# 04-RS485_CAN.net
KiCad netlist of a schematic drawn in Altium Designer
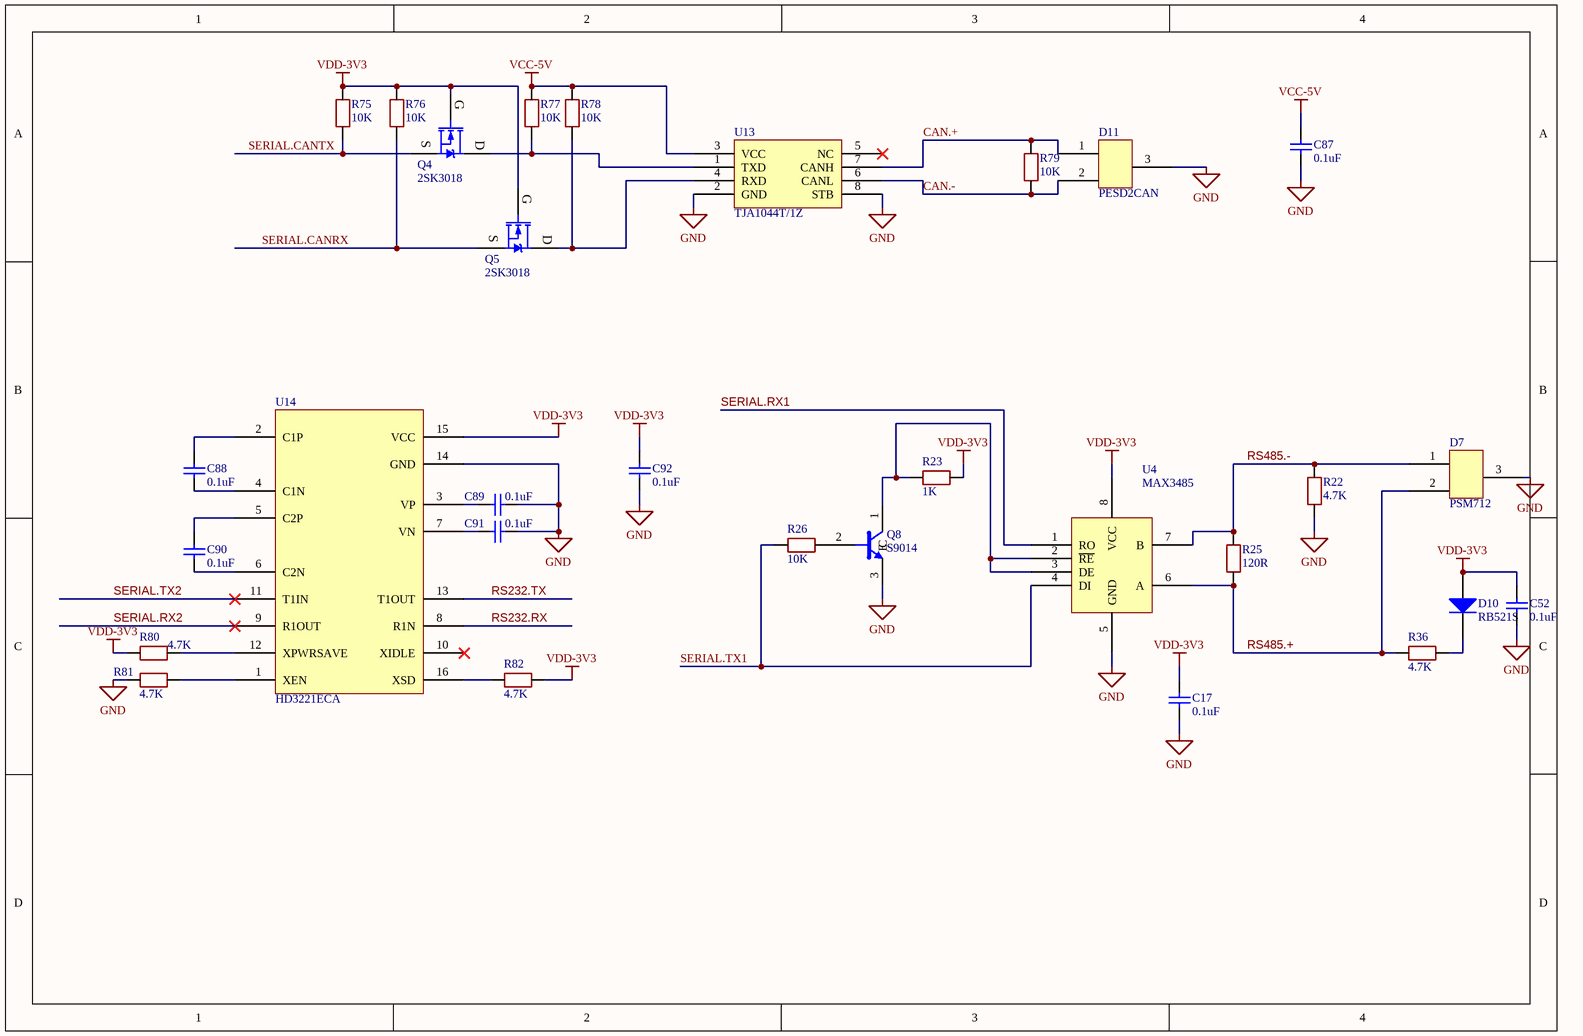
[diagram p0: 04-RS485+CAN.SchDoc]

(export (version "E")
  (design (tool "Eeschema 10.0.6"))
  (components
    (comp (ref "C17") (value "0.1uF") (footprint "C0402") (libsource (lib "PCB_Project") (part "CAP1")))
    (comp (ref "C52") (value "0.1uF") (footprint "C0402") (libsource (lib "PCB_Project") (part "CAP1")))
    (comp (ref "C87") (value "0.1uF") (footprint "C0402") (libsource (lib "PCB_Project") (part "CAP1")))
    (comp (ref "C88") (value "0.1uF") (footprint "C0402") (libsource (lib "PCB_Project") (part "CAP1")))
    (comp (ref "C89") (value "0.1uF") (footprint "C0402") (libsource (lib "PCB_Project") (part "CAP1")))
    (comp (ref "C90") (value "0.1uF") (footprint "C0402") (libsource (lib "PCB_Project") (part "CAP1")))
    (comp (ref "C91") (value "0.1uF") (footprint "C0402") (libsource (lib "PCB_Project") (part "CAP1")))
    (comp (ref "C92") (value "0.1uF") (footprint "C0402") (libsource (lib "PCB_Project") (part "CAP1")))
    (comp (ref "D7")
      (value "PSM712")
      (footprint "SOT-23-3_L3.0-W1.7-P0.95-LS2.9-BR")
      (libsource (lib "Schlib1") (part "PESD2CAN"))
    )
    (comp (ref "D10")
      (value "RB521S")
      (footprint "SOD-523_L1.2-W0.8-LS1.6-RD")
      (libsource (lib "PCB_Project") (part "DIODE"))
    )
    (comp (ref "D11")
      (value "PESD2CAN")
      (footprint "SOT-23-3_L3.0-W1.7-P0.95-LS2.9-BR")
      (libsource (lib "Schlib1") (part "PESD2CAN"))
    )
    (comp (ref "Q4")
      (value "2SK3018")
      (footprint "SOT-23-3_L2.9-W1.6-P1.90-LS2.8-BR")
      (libsource (lib "PCB_Project") (part "2N7002"))
    )
    (comp (ref "Q5")
      (value "2SK3018")
      (footprint "SOT-23-3_L2.9-W1.6-P1.90-LS2.8-BR")
      (libsource (lib "PCB_Project") (part "2N7002"))
    )
    (comp (ref "Q8")
      (value "S9014")
      (footprint "SOT-23-3_L2.9-W1.6-P1.90-LS2.8-BR")
      (libsource (lib "PCB_Project") (part "NPN"))
    )
    (comp (ref "R22") (value "4.7K") (footprint "R0402") (libsource (lib "PCB_Project") (part "R")))
    (comp (ref "R23") (value "1K") (footprint "R0402") (libsource (lib "PCB_Project") (part "R")))
    (comp (ref "R25") (value "120R") (footprint "R0402") (libsource (lib "PCB_Project") (part "R")))
    (comp (ref "R26") (value "10K") (footprint "R0402") (libsource (lib "PCB_Project") (part "R")))
    (comp (ref "R36") (value "4.7K") (footprint "R0402") (libsource (lib "PCB_Project") (part "R")))
    (comp (ref "R75") (value "10K") (footprint "R0402") (libsource (lib "PCB_Project") (part "R")))
    (comp (ref "R76") (value "10K") (footprint "R0402") (libsource (lib "PCB_Project") (part "R")))
    (comp (ref "R77") (value "10K") (footprint "R0402") (libsource (lib "PCB_Project") (part "R")))
    (comp (ref "R78") (value "10K") (footprint "R0402") (libsource (lib "PCB_Project") (part "R")))
    (comp (ref "R79") (value "10K") (footprint "R0402") (libsource (lib "PCB_Project") (part "R")))
    (comp (ref "R80") (value "4.7K") (footprint "R0402") (libsource (lib "PCB_Project") (part "R")))
    (comp (ref "R81") (value "4.7K") (footprint "R0402") (libsource (lib "PCB_Project") (part "R")))
    (comp (ref "R82") (value "4.7K") (footprint "R0402") (libsource (lib "PCB_Project") (part "R")))
    (comp (ref "U4")
      (value "MAX3485")
      (footprint "SOIC-8_L4.9-W3.9-P1.27-LS6.0-BL")
      (libsource (lib "Schlib1") (part "MAX3485"))
    )
    (comp (ref "U13")
      (value "TJA1044T/1Z")
      (footprint "SOIC-8_L4.9-W3.9-P1.27-LS6.0-BL")
      (libsource (lib "Schlib1") (part "TJA1044T/1Z"))
    )
    (comp (ref "U14")
      (value "HD3221ECA")
      (footprint "SSOP-16_L6.2-W5.3-P0.65-LS7.8-BL")
      (libsource (lib "Sheet2") (part "HD3221ECA"))
    )
  )
  (nets
    (net (code "1") (name "/CAN.+") (class "Default")
      (node (ref "D11") (pin "1") (pintype "passive"))
      (node (ref "R79") (pin "2") (pinfunction "2_2") (pintype "passive"))
      (node (ref "U13") (pin "7") (pinfunction "CANH_7") (pintype "passive"))
    )
    (net (code "2") (name "/CAN.-") (class "Default")
      (node (ref "D11") (pin "2") (pintype "passive"))
      (node (ref "R79") (pin "1") (pinfunction "1_1") (pintype "passive"))
      (node (ref "U13") (pin "6") (pinfunction "CANL_6") (pintype "passive"))
    )
    (net (code "3") (name "/RS232.RX") (class "Default")
      (node (ref "U14") (pin "8") (pinfunction "R1N_8") (pintype "passive"))
    )
    (net (code "4") (name "/RS232.TX") (class "Default")
      (node (ref "U14") (pin "13") (pinfunction "T1OUT_13") (pintype "passive"))
    )
    (net (code "5") (name "/RS485.+") (class "Default")
      (node (ref "D7") (pin "2") (pintype "passive"))
      (node (ref "R25") (pin "2") (pinfunction "2_2") (pintype "passive"))
      (node (ref "R36") (pin "2") (pinfunction "2_2") (pintype "passive"))
      (node (ref "U4") (pin "6") (pinfunction "A_6") (pintype "passive"))
    )
    (net (code "6") (name "/RS485.-") (class "Default")
      (node (ref "D7") (pin "1") (pintype "passive"))
      (node (ref "R22") (pin "1") (pinfunction "1_1") (pintype "passive"))
      (node (ref "R25") (pin "1") (pinfunction "1_1") (pintype "passive"))
      (node (ref "U4") (pin "7") (pinfunction "B_7") (pintype "passive"))
    )
    (net (code "7") (name "/SERIAL.CANRX") (class "Default")
      (node (ref "Q5") (pin "2") (pinfunction "S_2") (pintype "passive"))
      (node (ref "R76") (pin "1") (pinfunction "1_1") (pintype "passive"))
    )
    (net (code "8") (name "/SERIAL.CANTX") (class "Default")
      (node (ref "Q4") (pin "2") (pinfunction "S_2") (pintype "passive"))
      (node (ref "R75") (pin "1") (pinfunction "1_1") (pintype "passive"))
    )
    (net (code "9") (name "/SERIAL.RX1") (class "Default")
      (node (ref "U4") (pin "1") (pinfunction "RO_1") (pintype "passive"))
    )
    (net (code "10") (name "/SERIAL.RX2") (class "Default")
      (node (ref "U14") (pin "9") (pinfunction "R1OUT_9") (pintype "passive+no_connect"))
    )
    (net (code "11") (name "/SERIAL.TX1") (class "Default")
      (node (ref "R26") (pin "2") (pinfunction "2_2") (pintype "passive"))
      (node (ref "U4") (pin "4") (pinfunction "DI_4") (pintype "passive"))
    )
    (net (code "12") (name "/SERIAL.TX2") (class "Default")
      (node (ref "U14") (pin "11") (pinfunction "T1IN_11") (pintype "passive+no_connect"))
    )
    (net (code "13") (name "GND") (class "Default")
      (node (ref "C17") (pin "1") (pinfunction "1_1") (pintype "passive"))
      (node (ref "C52") (pin "1") (pinfunction "1_1") (pintype "passive"))
      (node (ref "C87") (pin "1") (pinfunction "1_1") (pintype "passive"))
      (node (ref "C89") (pin "1") (pinfunction "1_1") (pintype "passive"))
      (node (ref "C91") (pin "1") (pinfunction "1_1") (pintype "passive"))
      (node (ref "C92") (pin "1") (pinfunction "1_1") (pintype "passive"))
      (node (ref "D11") (pin "3") (pintype "passive"))
      (node (ref "D7") (pin "3") (pintype "passive"))
      (node (ref "Q8") (pin "3") (pinfunction "E_3") (pintype "passive"))
      (node (ref "R22") (pin "2") (pinfunction "2_2") (pintype "passive"))
      (node (ref "R81") (pin "2") (pinfunction "2_2") (pintype "passive"))
      (node (ref "U13") (pin "2") (pinfunction "GND_2") (pintype "passive"))
      (node (ref "U13") (pin "8") (pinfunction "STB_8") (pintype "passive"))
      (node (ref "U14") (pin "14") (pinfunction "GND_14") (pintype "passive"))
      (node (ref "U4") (pin "5") (pinfunction "GND_5") (pintype "passive"))
    )
    (net (code "14") (name "Net-(D10-K)") (class "Default")
      (node (ref "D10") (pin "2") (pinfunction "K_2") (pintype "passive"))
      (node (ref "R36") (pin "1") (pinfunction "1_1") (pintype "passive"))
    )
    (net (code "15") (name "Net-(Q4-D)") (class "Default")
      (node (ref "Q4") (pin "3") (pinfunction "D_3") (pintype "passive"))
      (node (ref "R77") (pin "1") (pinfunction "1_1") (pintype "passive"))
      (node (ref "U13") (pin "1") (pinfunction "TXD_1") (pintype "passive"))
    )
    (net (code "16") (name "Net-(Q5-D)") (class "Default")
      (node (ref "Q5") (pin "3") (pinfunction "D_3") (pintype "passive"))
      (node (ref "R78") (pin "1") (pinfunction "1_1") (pintype "passive"))
      (node (ref "U13") (pin "4") (pinfunction "RXD_4") (pintype "passive"))
    )
    (net (code "17") (name "Net-(Q8-B)") (class "Default")
      (node (ref "Q8") (pin "2") (pinfunction "B_2") (pintype "passive"))
      (node (ref "R26") (pin "1") (pinfunction "1_1") (pintype "passive"))
    )
    (net (code "18") (name "Net-(Q8-C)") (class "Default")
      (node (ref "Q8") (pin "1") (pinfunction "C_1") (pintype "passive"))
      (node (ref "R23") (pin "2") (pinfunction "2_2") (pintype "passive"))
      (node (ref "U4") (pin "2") (pinfunction "~{RE}_2") (pintype "passive"))
      (node (ref "U4") (pin "3") (pinfunction "DE_3") (pintype "passive"))
    )
    (net (code "19") (name "Net-(U14-C1N)") (class "Default")
      (node (ref "C88") (pin "1") (pinfunction "1_1") (pintype "passive"))
      (node (ref "U14") (pin "4") (pinfunction "C1N_4") (pintype "passive"))
    )
    (net (code "20") (name "Net-(U14-C1P)") (class "Default")
      (node (ref "C88") (pin "2") (pinfunction "2_2") (pintype "passive"))
      (node (ref "U14") (pin "2") (pinfunction "C1P_2") (pintype "passive"))
    )
    (net (code "21") (name "Net-(U14-C2N)") (class "Default")
      (node (ref "C90") (pin "1") (pinfunction "1_1") (pintype "passive"))
      (node (ref "U14") (pin "6") (pinfunction "C2N_6") (pintype "passive"))
    )
    (net (code "22") (name "Net-(U14-C2P)") (class "Default")
      (node (ref "C90") (pin "2") (pinfunction "2_2") (pintype "passive"))
      (node (ref "U14") (pin "5") (pinfunction "C2P_5") (pintype "passive"))
    )
    (net (code "23") (name "Net-(U14-VN)") (class "Default")
      (node (ref "C91") (pin "2") (pinfunction "2_2") (pintype "passive"))
      (node (ref "U14") (pin "7") (pinfunction "VN_7") (pintype "passive"))
    )
    (net (code "24") (name "Net-(U14-VP)") (class "Default")
      (node (ref "C89") (pin "2") (pinfunction "2_2") (pintype "passive"))
      (node (ref "U14") (pin "3") (pinfunction "VP_3") (pintype "passive"))
    )
    (net (code "25") (name "Net-(U14-XEN)") (class "Default")
      (node (ref "R81") (pin "1") (pinfunction "1_1") (pintype "passive"))
      (node (ref "U14") (pin "1") (pinfunction "XEN_1") (pintype "passive"))
    )
    (net (code "26") (name "Net-(U14-XPWRSAVE)") (class "Default")
      (node (ref "R80") (pin "1") (pinfunction "1_1") (pintype "passive"))
      (node (ref "U14") (pin "12") (pinfunction "XPWRSAVE_12") (pintype "passive"))
    )
    (net (code "27") (name "Net-(U14-XSD)") (class "Default")
      (node (ref "R82") (pin "2") (pinfunction "2_2") (pintype "passive"))
      (node (ref "U14") (pin "16") (pinfunction "XSD_16") (pintype "passive"))
    )
    (net (code "28") (name "VCC-5V") (class "Default")
      (node (ref "C87") (pin "2") (pinfunction "2_2") (pintype "passive"))
      (node (ref "R77") (pin "2") (pinfunction "2_2") (pintype "passive"))
      (node (ref "R78") (pin "2") (pinfunction "2_2") (pintype "passive"))
      (node (ref "U13") (pin "3") (pinfunction "VCC_3") (pintype "passive"))
    )
    (net (code "29") (name "VDD-3V3") (class "Default")
      (node (ref "C17") (pin "2") (pinfunction "2_2") (pintype "passive"))
      (node (ref "C52") (pin "2") (pinfunction "2_2") (pintype "passive"))
      (node (ref "C92") (pin "2") (pinfunction "2_2") (pintype "passive"))
      (node (ref "D10") (pin "1") (pinfunction "A_1") (pintype "passive"))
      (node (ref "Q4") (pin "1") (pinfunction "G_1") (pintype "passive"))
      (node (ref "Q5") (pin "1") (pinfunction "G_1") (pintype "passive"))
      (node (ref "R23") (pin "1") (pinfunction "1_1") (pintype "passive"))
      (node (ref "R75") (pin "2") (pinfunction "2_2") (pintype "passive"))
      (node (ref "R76") (pin "2") (pinfunction "2_2") (pintype "passive"))
      (node (ref "R80") (pin "2") (pinfunction "2_2") (pintype "passive"))
      (node (ref "R82") (pin "1") (pinfunction "1_1") (pintype "passive"))
      (node (ref "U14") (pin "15") (pinfunction "VCC_15") (pintype "passive"))
      (node (ref "U4") (pin "8") (pinfunction "VCC_8") (pintype "passive"))
    )
    (net (code "30") (name "unconnected-(U13-NC-Pad5)") (class "Default")
      (node (ref "U13") (pin "5") (pinfunction "NC_5") (pintype "passive+no_connect"))
    )
    (net (code "31") (name "unconnected-(U14-XIDLE-Pad10)") (class "Default")
      (node (ref "U14") (pin "10") (pinfunction "XIDLE_10") (pintype "passive+no_connect"))
    )
  )
)
